# motor_driver.net
KiCad netlist of a schematic drawn in EasyEDA Pro
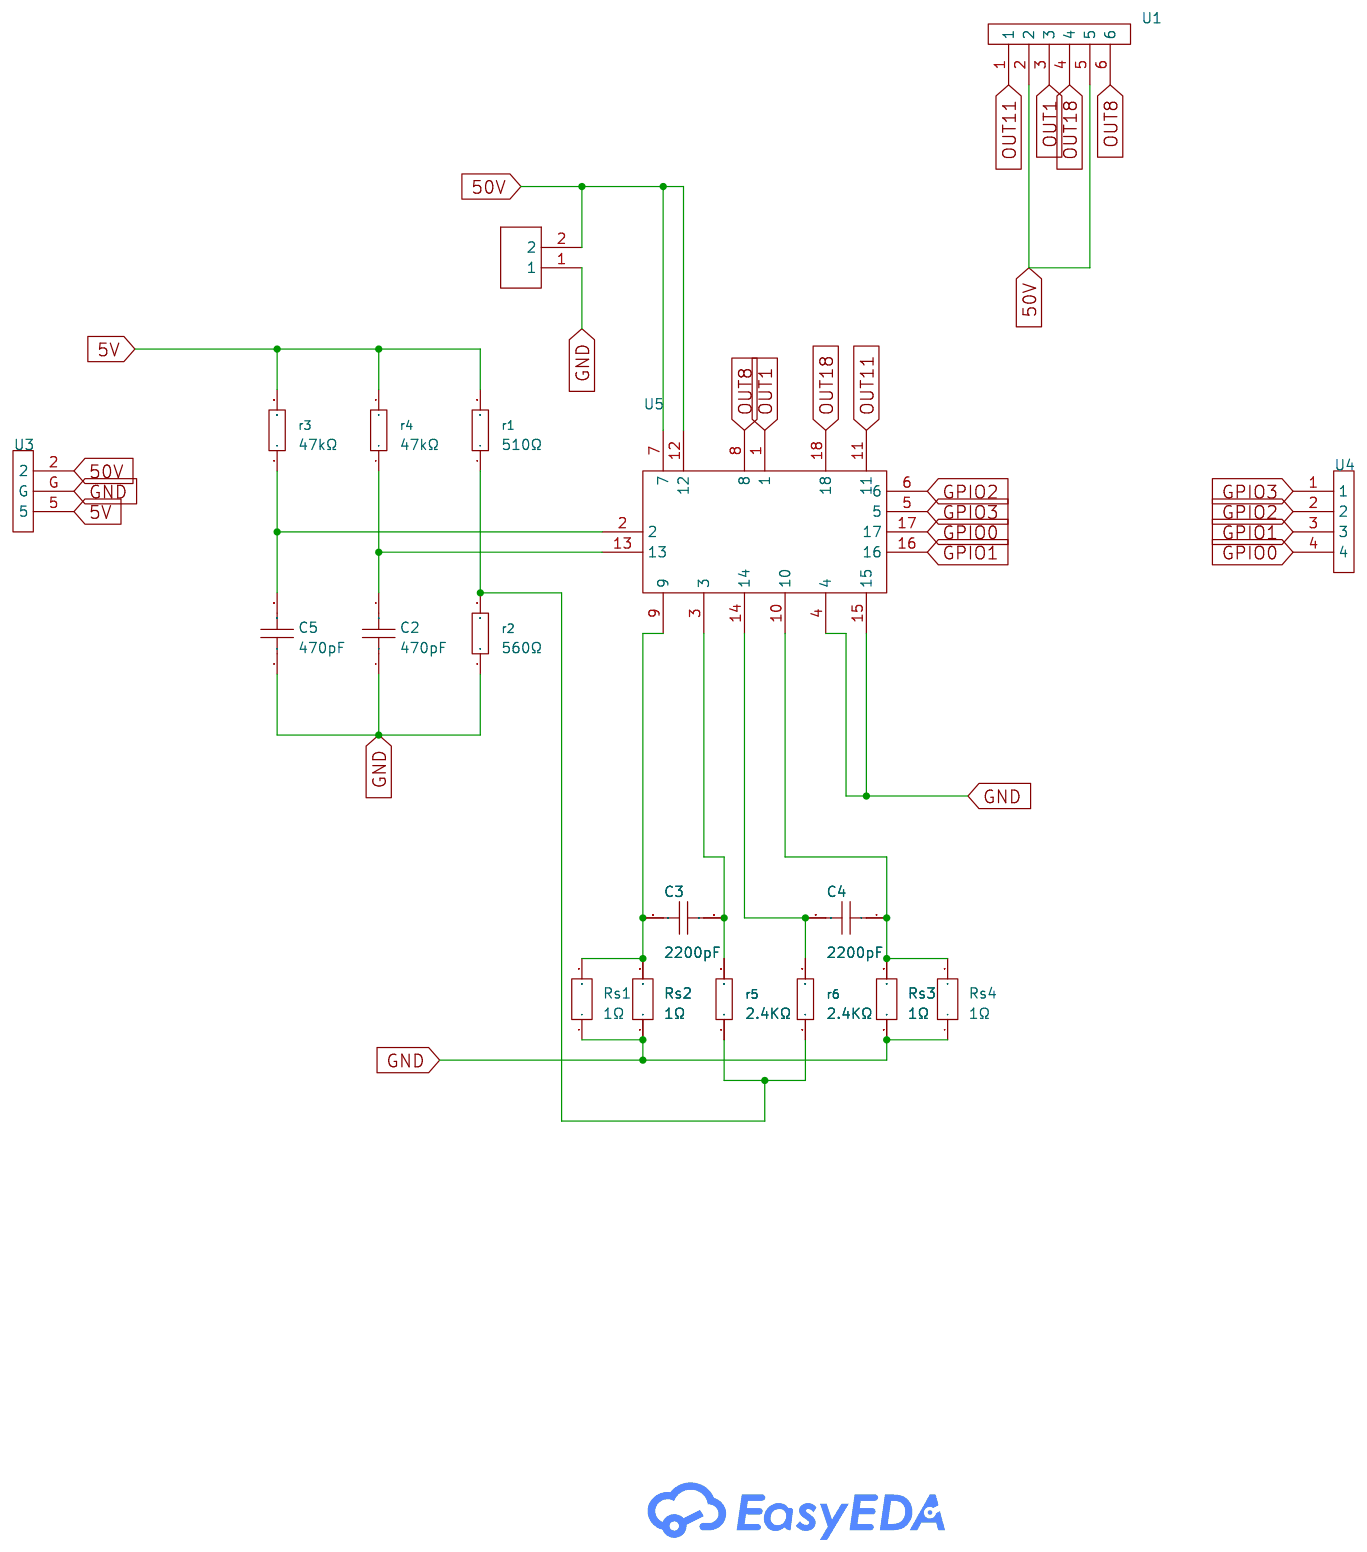
[diagram p0: schematic sheet]

(export (version "E")
  (design (tool "Eeschema 10.0.6"))
  (components
    (comp (ref "C1")
      (value "~")
      (footprint "easyedapro:100uF Capacitor")
      (libsource (lib "easyedapro") (part "100uF Capacitor"))
    )
    (comp (ref "C2")
      (value "470pF")
      (footprint "easyedapro:C0603")
      (description "Capacitance:2.2uF Tolerance:±10% Tolerance:±10% Voltage Rating:25V Temperature Coefficient:X7S")
      (fields
        (field (name "Manufacturer Part") "CL10Y225KA96PNC")
        (field (name "Manufacturer") "SAMSUNG(三星)")
      )
      (libsource (lib "easyedapro") (part "CL10Y225KA96PNC"))
    )
    (comp (ref "C3")
      (value "2200pF")
      (footprint "easyedapro:C0603")
      (description "Capacitance:2.2uF Tolerance:±10% Tolerance:±10% Voltage Rating:25V Temperature Coefficient:X7S")
      (fields
        (field (name "Manufacturer Part") "CL10Y225KA96PNC")
        (field (name "Manufacturer") "SAMSUNG(三星)")
      )
      (libsource (lib "easyedapro") (part "CL10Y225KA96PNC"))
    )
    (comp (ref "C4")
      (value "2200pF")
      (footprint "easyedapro:C0603")
      (description "Capacitance:2.2uF Tolerance:±10% Tolerance:±10% Voltage Rating:25V Temperature Coefficient:X7S")
      (fields
        (field (name "Manufacturer Part") "CL10Y225KA96PNC")
        (field (name "Manufacturer") "SAMSUNG(三星)")
      )
      (libsource (lib "easyedapro") (part "CL10Y225KA96PNC"))
    )
    (comp (ref "C5")
      (value "470pF")
      (footprint "easyedapro:C0603")
      (description "Capacitance:2.2uF Tolerance:±10% Tolerance:±10% Voltage Rating:25V Temperature Coefficient:X7S")
      (fields
        (field (name "Manufacturer Part") "CL10Y225KA96PNC")
        (field (name "Manufacturer") "SAMSUNG(三星)")
      )
      (libsource (lib "easyedapro") (part "CL10Y225KA96PNC"))
    )
    (comp (ref "r1")
      (value "510Ω")
      (footprint "easyedapro:R0603")
      (fields
        (field (name "Manufacturer Part") "0603WAF1005T5E")
        (field (name "Manufacturer") "UNI-ROYAL(厚声)")
      )
      (libsource (lib "easyedapro") (part "0603WAF1005T5E"))
    )
    (comp (ref "r2")
      (value "560Ω")
      (footprint "easyedapro:R0603")
      (fields
        (field (name "Manufacturer Part") "0603WAF1005T5E")
        (field (name "Manufacturer") "UNI-ROYAL(厚声)")
      )
      (libsource (lib "easyedapro") (part "0603WAF1005T5E"))
    )
    (comp (ref "r3")
      (value "47kΩ")
      (footprint "easyedapro:R0603")
      (fields
        (field (name "Manufacturer Part") "0603WAF1005T5E")
        (field (name "Manufacturer") "UNI-ROYAL(厚声)")
      )
      (libsource (lib "easyedapro") (part "0603WAF1005T5E"))
    )
    (comp (ref "r4")
      (value "47kΩ")
      (footprint "easyedapro:R0603")
      (fields
        (field (name "Manufacturer Part") "0603WAF1005T5E")
        (field (name "Manufacturer") "UNI-ROYAL(厚声)")
      )
      (libsource (lib "easyedapro") (part "0603WAF1005T5E"))
    )
    (comp (ref "r5")
      (value "2.4KΩ")
      (footprint "easyedapro:R0603")
      (fields
        (field (name "Manufacturer Part") "0603WAF1005T5E")
        (field (name "Manufacturer") "UNI-ROYAL(厚声)")
      )
      (libsource (lib "easyedapro") (part "0603WAF1005T5E"))
    )
    (comp (ref "r6")
      (value "2.4KΩ")
      (footprint "easyedapro:R0603")
      (fields
        (field (name "Manufacturer Part") "0603WAF1005T5E")
        (field (name "Manufacturer") "UNI-ROYAL(厚声)")
      )
      (libsource (lib "easyedapro") (part "0603WAF1005T5E"))
    )
    (comp (ref "Rs1")
      (value "1Ω")
      (footprint "easyedapro:R2512")
      (fields
        (field (name "Manufacturer Part") "HoYLR2512-2W-50mR-1%")
        (field (name "Manufacturer") "Milliohm(毫欧)")
      )
      (libsource (lib "easyedapro") (part "HOYLR2512-2W-50MR-1%"))
    )
    (comp (ref "Rs2")
      (value "1Ω")
      (footprint "easyedapro:R2512")
      (fields
        (field (name "Manufacturer Part") "HoYLR2512-2W-50mR-1%")
        (field (name "Manufacturer") "Milliohm(毫欧)")
      )
      (libsource (lib "easyedapro") (part "HOYLR2512-2W-50MR-1%"))
    )
    (comp (ref "Rs3")
      (value "1Ω")
      (footprint "easyedapro:R2512")
      (fields
        (field (name "Manufacturer Part") "HoYLR2512-2W-50mR-1%")
        (field (name "Manufacturer") "Milliohm(毫欧)")
      )
      (libsource (lib "easyedapro") (part "HOYLR2512-2W-50MR-1%"))
    )
    (comp (ref "Rs4")
      (value "1Ω")
      (footprint "easyedapro:R2512")
      (fields
        (field (name "Manufacturer Part") "HoYLR2512-2W-50mR-1%")
        (field (name "Manufacturer") "Milliohm(毫欧)")
      )
      (libsource (lib "easyedapro") (part "HOYLR2512-2W-50MR-1%"))
    )
    (comp (ref "U1") (value "~") (libsource (lib "easyedapro") (part "6pin")))
    (comp (ref "U3")
      (value "~")
      (footprint "easyedapro:3_waper")
      (libsource (lib "easyedapro") (part "3_waper"))
    )
    (comp (ref "U4") (value "~") (footprint "easyedapro:4pin") (libsource (lib "easyedapro") (part "4pin")))
    (comp (ref "U5")
      (value "~")
      (footprint "easyedapro:SLA7026M")
      (libsource (lib "easyedapro") (part "SLA7026M"))
    )
  )
  (nets
    (net (code "1") (name "5V") (class "Default")
      (node (ref "U3") (pin "5") (pinfunction "5_5") (pintype "input"))
      (node (ref "r1") (pin "2") (pinfunction "2_2") (pintype "input"))
      (node (ref "r3") (pin "2") (pinfunction "2_2") (pintype "input"))
      (node (ref "r4") (pin "2") (pinfunction "2_2") (pintype "input"))
    )
    (net (code "2") (name "50V") (class "Default")
      (node (ref "C1") (pin "2") (pinfunction "2_2") (pintype "input"))
      (node (ref "U1") (pin "2") (pinfunction "2_2") (pintype "input"))
      (node (ref "U1") (pin "5") (pinfunction "5_5") (pintype "input"))
      (node (ref "U3") (pin "2") (pinfunction "2_2") (pintype "input"))
      (node (ref "U5") (pin "12") (pinfunction "12_12") (pintype "input"))
      (node (ref "U5") (pin "7") (pinfunction "7_7") (pintype "input"))
    )
    (net (code "3") (name "GND") (class "Default")
      (node (ref "C1") (pin "1") (pinfunction "1_1") (pintype "input"))
      (node (ref "C2") (pin "1") (pinfunction "1_1") (pintype "unspecified"))
      (node (ref "C5") (pin "1") (pinfunction "1_1") (pintype "unspecified"))
      (node (ref "Rs1") (pin "1") (pinfunction "1_1") (pintype "unspecified"))
      (node (ref "Rs2") (pin "1") (pinfunction "1_1") (pintype "unspecified"))
      (node (ref "Rs3") (pin "1") (pinfunction "1_1") (pintype "unspecified"))
      (node (ref "Rs4") (pin "1") (pinfunction "1_1") (pintype "unspecified"))
      (node (ref "U3") (pin "G") (pinfunction "G_G") (pintype "input"))
      (node (ref "U5") (pin "15") (pinfunction "15_15") (pintype "input"))
      (node (ref "U5") (pin "4") (pinfunction "4_4") (pintype "input"))
      (node (ref "r2") (pin "1") (pinfunction "1_1") (pintype "input"))
    )
    (net (code "4") (name "GPIO0") (class "Default")
      (node (ref "U4") (pin "4") (pinfunction "4_4") (pintype "input"))
      (node (ref "U5") (pin "17") (pinfunction "17_17") (pintype "input"))
    )
    (net (code "5") (name "GPIO1") (class "Default")
      (node (ref "U4") (pin "3") (pinfunction "3_3") (pintype "input"))
      (node (ref "U5") (pin "16") (pinfunction "16_16") (pintype "input"))
    )
    (net (code "6") (name "GPIO2") (class "Default")
      (node (ref "U4") (pin "2") (pinfunction "2_2") (pintype "input"))
      (node (ref "U5") (pin "6") (pinfunction "6_6") (pintype "input"))
    )
    (net (code "7") (name "GPIO3") (class "Default")
      (node (ref "U4") (pin "1") (pinfunction "1_1") (pintype "input"))
      (node (ref "U5") (pin "5") (pinfunction "5_5") (pintype "input"))
    )
    (net (code "8") (name "Net-(C2-Pad2)") (class "Default")
      (node (ref "C2") (pin "2") (pinfunction "2_2") (pintype "unspecified"))
      (node (ref "U5") (pin "13") (pinfunction "13_13") (pintype "input"))
      (node (ref "r4") (pin "1") (pinfunction "1_1") (pintype "input"))
    )
    (net (code "9") (name "Net-(C3-Pad1)") (class "Default")
      (node (ref "C3") (pin "1") (pinfunction "1_1") (pintype "unspecified"))
      (node (ref "U5") (pin "3") (pinfunction "3_3") (pintype "input"))
      (node (ref "r5") (pin "2") (pinfunction "2_2") (pintype "input"))
    )
    (net (code "10") (name "Net-(C3-Pad2)") (class "Default")
      (node (ref "C3") (pin "2") (pinfunction "2_2") (pintype "unspecified"))
      (node (ref "Rs1") (pin "2") (pinfunction "2_2") (pintype "unspecified"))
      (node (ref "Rs2") (pin "2") (pinfunction "2_2") (pintype "unspecified"))
      (node (ref "U5") (pin "9") (pinfunction "9_9") (pintype "input"))
    )
    (net (code "11") (name "Net-(C4-Pad1)") (class "Default")
      (node (ref "C4") (pin "1") (pinfunction "1_1") (pintype "unspecified"))
      (node (ref "Rs3") (pin "2") (pinfunction "2_2") (pintype "unspecified"))
      (node (ref "Rs4") (pin "2") (pinfunction "2_2") (pintype "unspecified"))
      (node (ref "U5") (pin "10") (pinfunction "10_10") (pintype "input"))
    )
    (net (code "12") (name "Net-(C4-Pad2)") (class "Default")
      (node (ref "C4") (pin "2") (pinfunction "2_2") (pintype "unspecified"))
      (node (ref "U5") (pin "14") (pinfunction "14_14") (pintype "input"))
      (node (ref "r6") (pin "2") (pinfunction "2_2") (pintype "input"))
    )
    (net (code "13") (name "Net-(C5-Pad2)") (class "Default")
      (node (ref "C5") (pin "2") (pinfunction "2_2") (pintype "unspecified"))
      (node (ref "U5") (pin "2") (pinfunction "2_2") (pintype "input"))
      (node (ref "r3") (pin "1") (pinfunction "1_1") (pintype "input"))
    )
    (net (code "14") (name "Net-(r1-Pad1)") (class "Default")
      (node (ref "r1") (pin "1") (pinfunction "1_1") (pintype "input"))
      (node (ref "r2") (pin "2") (pinfunction "2_2") (pintype "input"))
      (node (ref "r5") (pin "1") (pinfunction "1_1") (pintype "input"))
      (node (ref "r6") (pin "1") (pinfunction "1_1") (pintype "input"))
    )
    (net (code "15") (name "OUT1") (class "Default")
      (node (ref "U1") (pin "3") (pinfunction "3_3") (pintype "input"))
      (node (ref "U5") (pin "1") (pinfunction "1_1") (pintype "input"))
    )
    (net (code "16") (name "OUT8") (class "Default")
      (node (ref "U1") (pin "6") (pinfunction "6_6") (pintype "input"))
      (node (ref "U5") (pin "8") (pinfunction "8_8") (pintype "input"))
    )
    (net (code "17") (name "OUT11") (class "Default")
      (node (ref "U1") (pin "1") (pinfunction "1_1") (pintype "input"))
      (node (ref "U5") (pin "11") (pinfunction "11_11") (pintype "input"))
    )
    (net (code "18") (name "OUT18") (class "Default")
      (node (ref "U1") (pin "4") (pinfunction "4_4") (pintype "input"))
      (node (ref "U5") (pin "18") (pinfunction "18_18") (pintype "input"))
    )
  )
)
